# MainBoard_V100_DISP.net
KiCad netlist of a schematic drawn in Altium Designer
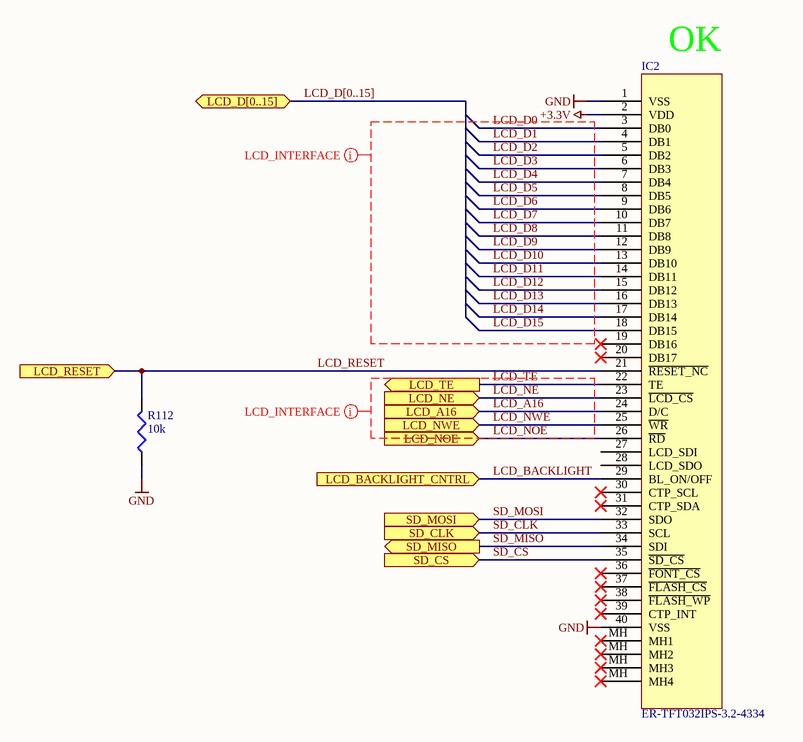
[diagram p0: MainBoard_V100_DISP.SchDoc]

(export (version "E")
  (design (tool "Eeschema 10.0.6"))
  (components
    (comp (ref "IC2")
      (value "ER-TFT032IPS-3.2-4334")
      (footprint "ER-TFT032IPS-3.2")
      (description "3.2 inch 240x320 IPS TFT LCD Module")
      (libsource (lib "ALTIUM_DB_LIB") (part "ER-TFT032IPS-3.2"))
    )
    (comp (ref "R112")
      (value "10k")
      (footprint "0805")
      (description "10k 0805 0.125W 1%")
      (fields (field (name "PART NUMBER") "SMD0805-10k 1%"))
      (libsource (lib "ALTIUM_DB_LIB") (part "RESISTOR"))
    )
  )
  (nets
    (net (code "1") (name "+3.3V") (class "Default")
      (node (ref "IC2") (pin "2") (pinfunction "VDD_2") (pintype "passive"))
    )
    (net (code "2") (name "/LCD_A16") (class "Default")
      (node (ref "IC2") (pin "24") (pinfunction "D/C_24") (pintype "passive"))
    )
    (net (code "3") (name "/LCD_BACKLIGHT") (class "Default")
      (node (ref "IC2") (pin "29") (pinfunction "BL_ON/OFF_29") (pintype "passive"))
    )
    (net (code "4") (name "/LCD_D0") (class "Default")
      (node (ref "IC2") (pin "3") (pinfunction "DB0_3") (pintype "passive"))
    )
    (net (code "5") (name "/LCD_D1") (class "Default")
      (node (ref "IC2") (pin "4") (pinfunction "DB1_4") (pintype "passive"))
    )
    (net (code "6") (name "/LCD_D2") (class "Default")
      (node (ref "IC2") (pin "5") (pinfunction "DB2_5") (pintype "passive"))
    )
    (net (code "7") (name "/LCD_D3") (class "Default")
      (node (ref "IC2") (pin "6") (pinfunction "DB3_6") (pintype "passive"))
    )
    (net (code "8") (name "/LCD_D4") (class "Default")
      (node (ref "IC2") (pin "7") (pinfunction "DB4_7") (pintype "passive"))
    )
    (net (code "9") (name "/LCD_D5") (class "Default")
      (node (ref "IC2") (pin "8") (pinfunction "DB5_8") (pintype "passive"))
    )
    (net (code "10") (name "/LCD_D6") (class "Default")
      (node (ref "IC2") (pin "9") (pinfunction "DB6_9") (pintype "passive"))
    )
    (net (code "11") (name "/LCD_D7") (class "Default")
      (node (ref "IC2") (pin "10") (pinfunction "DB7_10") (pintype "passive"))
    )
    (net (code "12") (name "/LCD_D8") (class "Default")
      (node (ref "IC2") (pin "11") (pinfunction "DB8_11") (pintype "passive"))
    )
    (net (code "13") (name "/LCD_D9") (class "Default")
      (node (ref "IC2") (pin "12") (pinfunction "DB9_12") (pintype "passive"))
    )
    (net (code "14") (name "/LCD_D10") (class "Default")
      (node (ref "IC2") (pin "13") (pinfunction "DB10_13") (pintype "passive"))
    )
    (net (code "15") (name "/LCD_D11") (class "Default")
      (node (ref "IC2") (pin "14") (pinfunction "DB11_14") (pintype "passive"))
    )
    (net (code "16") (name "/LCD_D12") (class "Default")
      (node (ref "IC2") (pin "15") (pinfunction "DB12_15") (pintype "passive"))
    )
    (net (code "17") (name "/LCD_D13") (class "Default")
      (node (ref "IC2") (pin "16") (pinfunction "DB13_16") (pintype "passive"))
    )
    (net (code "18") (name "/LCD_D14") (class "Default")
      (node (ref "IC2") (pin "17") (pinfunction "DB14_17") (pintype "passive"))
    )
    (net (code "19") (name "/LCD_D15") (class "Default")
      (node (ref "IC2") (pin "18") (pinfunction "DB15_18") (pintype "passive"))
    )
    (net (code "21") (name "/LCD_NE") (class "Default")
      (node (ref "IC2") (pin "23") (pinfunction "~{LCD_CS}_23") (pintype "passive"))
    )
    (net (code "22") (name "/LCD_NOE") (class "Default")
      (node (ref "IC2") (pin "26") (pinfunction "~{RD}_26") (pintype "passive"))
    )
    (net (code "23") (name "/LCD_NWE") (class "Default")
      (node (ref "IC2") (pin "25") (pinfunction "~{WR}_25") (pintype "passive"))
    )
    (net (code "24") (name "/LCD_RESET") (class "Default")
      (node (ref "IC2") (pin "21") (pinfunction "~{RESET_NC}_21") (pintype "passive"))
      (node (ref "R112") (pin "2") (pintype "passive"))
    )
    (net (code "25") (name "/LCD_TE") (class "Default")
      (node (ref "IC2") (pin "22") (pinfunction "TE_22") (pintype "passive"))
    )
    (net (code "26") (name "/SD_CLK") (class "Default")
      (node (ref "IC2") (pin "33") (pinfunction "SCL_33") (pintype "passive"))
    )
    (net (code "27") (name "/SD_CS") (class "Default")
      (node (ref "IC2") (pin "35") (pinfunction "~{SD_CS}_35") (pintype "passive"))
    )
    (net (code "28") (name "/SD_MISO") (class "Default")
      (node (ref "IC2") (pin "34") (pinfunction "SDI_34") (pintype "passive"))
    )
    (net (code "29") (name "/SD_MOSI") (class "Default")
      (node (ref "IC2") (pin "32") (pinfunction "SDO_32") (pintype "passive"))
    )
    (net (code "30") (name "GND") (class "Default")
      (node (ref "IC2") (pin "1") (pinfunction "VSS_1") (pintype "passive"))
      (node (ref "IC2") (pin "40") (pinfunction "VSS_40") (pintype "passive"))
      (node (ref "R112") (pin "1") (pintype "passive"))
    )
    (net (code "31") (name "unconnected-(IC2-CTP_INT-Pad39)") (class "Default")
      (node (ref "IC2") (pin "39") (pinfunction "CTP_INT_39") (pintype "passive+no_connect"))
    )
    (net (code "32") (name "unconnected-(IC2-CTP_SCL-Pad30)") (class "Default")
      (node (ref "IC2") (pin "30") (pinfunction "CTP_SCL_30") (pintype "passive+no_connect"))
    )
    (net (code "33") (name "unconnected-(IC2-CTP_SDA-Pad31)") (class "Default")
      (node (ref "IC2") (pin "31") (pinfunction "CTP_SDA_31") (pintype "passive+no_connect"))
    )
    (net (code "34") (name "unconnected-(IC2-DB16-Pad19)") (class "Default")
      (node (ref "IC2") (pin "19") (pinfunction "DB16_19") (pintype "passive+no_connect"))
    )
    (net (code "35") (name "unconnected-(IC2-DB17-Pad20)") (class "Default")
      (node (ref "IC2") (pin "20") (pinfunction "DB17_20") (pintype "passive+no_connect"))
    )
    (net (code "36") (name "unconnected-(IC2-LCD_SDI-Pad27)") (class "Default")
      (node (ref "IC2") (pin "27") (pinfunction "LCD_SDI_27") (pintype "passive"))
    )
    (net (code "37") (name "unconnected-(IC2-LCD_SDO-Pad28)") (class "Default")
      (node (ref "IC2") (pin "28") (pinfunction "LCD_SDO_28") (pintype "passive"))
    )
    (net (code "38") (name "unconnected-(IC2-MH1-PadMH)") (class "Default")
      (node (ref "IC2") (pin "MH") (pinfunction "MH1_MH") (pintype "passive+no_connect"))
    )
    (net (code "39") (name "unconnected-(IC2-MH2-PadMH)") (class "Default")
      (node (ref "IC2") (pin "MH") (pinfunction "MH2_MH") (pintype "passive+no_connect"))
    )
    (net (code "40") (name "unconnected-(IC2-MH3-PadMH)") (class "Default")
      (node (ref "IC2") (pin "MH") (pinfunction "MH3_MH") (pintype "passive+no_connect"))
    )
    (net (code "41") (name "unconnected-(IC2-MH4-PadMH)") (class "Default")
      (node (ref "IC2") (pin "MH") (pinfunction "MH4_MH") (pintype "passive+no_connect"))
    )
    (net (code "42") (name "unconnected-(IC2-~{FLASH_CS}-Pad37)") (class "Default")
      (node (ref "IC2") (pin "37") (pinfunction "~{FLASH_CS}_37") (pintype "passive+no_connect"))
    )
    (net (code "43") (name "unconnected-(IC2-~{FLASH_WP}-Pad38)") (class "Default")
      (node (ref "IC2") (pin "38") (pinfunction "~{FLASH_WP}_38") (pintype "passive+no_connect"))
    )
    (net (code "44") (name "unconnected-(IC2-~{FONT_CS}-Pad36)") (class "Default")
      (node (ref "IC2") (pin "36") (pinfunction "~{FONT_CS}_36") (pintype "passive+no_connect"))
    )
  )
)
